# reza-power.net
KiCad netlist of a schematic drawn in EAGLE
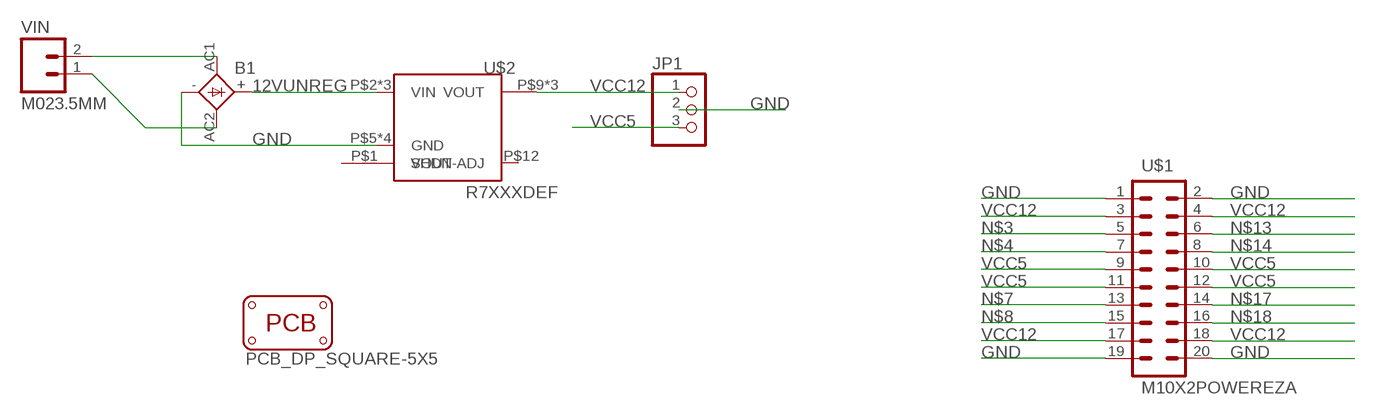
[diagram p0: schematic, sheet 1]

(export (version "E")
  (design (tool "Eeschema 10.0.6"))
  (components
    (comp (ref "B1")
      (value "1KAB")
      (footprint "eagle-import:1KAB")
      (libsource (lib "eagle-import") (part "1KAB"))
    )
    (comp (ref "JP1")
      (value "PINHD-1X3CB")
      (footprint "eagle-import:1X03-CLEANBIG")
      (libsource (lib "eagle-import") (part "PINHD-1X3CB"))
    )
    (comp (ref "PCB1")
      (value "PCB_DP_SQUARE-5X5")
      (footprint "eagle-import:DP5050_V1")
      (libsource (lib "eagle-import") (part "PCB_DP_SQUARE-5X5"))
    )
    (comp (ref "U$1")
      (value "M10X2POWEREZA")
      (footprint "eagle-import:REZAPOWER_INTERBOARD")
      (libsource (lib "eagle-import") (part "M10X2POWEREZA"))
    )
    (comp (ref "U$2")
      (value "R7XXXDEF")
      (footprint "eagle-import:1X12_RECOM")
      (libsource (lib "eagle-import") (part "R7XXXDEF"))
    )
    (comp (ref "VIN")
      (value "M023.5MM")
      (footprint "eagle-import:SCREWTERMINAL-3.5MM-2")
      (libsource (lib "eagle-import") (part "M023.5MM"))
    )
  )
  (nets
    (net (code "1") (name "/12VUNREG") (class "Default")
      (node (ref "B1") (pin "+") (pinfunction "+_+") (pintype "passive"))
      (node (ref "U$2") (pin "P$2") (pinfunction "VIN_P$2") (pintype "bidirectional"))
      (node (ref "U$2") (pin "P$3") (pinfunction "VIN_P$3") (pintype "bidirectional"))
      (node (ref "U$2") (pin "P$4") (pinfunction "VIN_P$4") (pintype "bidirectional"))
    )
    (net (code "2") (name "/GND") (class "Default")
      (node (ref "B1") (pin "-") (pinfunction "-_-") (pintype "passive"))
      (node (ref "JP1") (pin "2") (pinfunction "2_2") (pintype "passive"))
      (node (ref "U$1") (pin "1") (pinfunction "1_1") (pintype "passive"))
      (node (ref "U$1") (pin "19") (pinfunction "19_19") (pintype "passive"))
      (node (ref "U$1") (pin "2") (pinfunction "2_2") (pintype "passive"))
      (node (ref "U$1") (pin "20") (pinfunction "20_20") (pintype "passive"))
      (node (ref "U$2") (pin "P$5") (pinfunction "GND_P$5") (pintype "bidirectional"))
      (node (ref "U$2") (pin "P$6") (pinfunction "GND_P$6") (pintype "bidirectional"))
      (node (ref "U$2") (pin "P$7") (pinfunction "GND_P$7") (pintype "bidirectional"))
      (node (ref "U$2") (pin "P$8") (pinfunction "GND_P$8") (pintype "bidirectional"))
    )
    (net (code "3") (name "/N$3") (class "Default")
      (node (ref "U$1") (pin "5") (pinfunction "5_5") (pintype "passive"))
    )
    (net (code "4") (name "/N$4") (class "Default")
      (node (ref "U$1") (pin "7") (pinfunction "7_7") (pintype "passive"))
    )
    (net (code "5") (name "/N$7") (class "Default")
      (node (ref "U$1") (pin "13") (pinfunction "13_13") (pintype "passive"))
    )
    (net (code "6") (name "/N$8") (class "Default")
      (node (ref "U$1") (pin "15") (pinfunction "15_15") (pintype "passive"))
    )
    (net (code "7") (name "/N$13") (class "Default")
      (node (ref "U$1") (pin "6") (pinfunction "6_6") (pintype "passive"))
    )
    (net (code "8") (name "/N$14") (class "Default")
      (node (ref "U$1") (pin "8") (pinfunction "8_8") (pintype "passive"))
    )
    (net (code "9") (name "/N$17") (class "Default")
      (node (ref "U$1") (pin "14") (pinfunction "14_14") (pintype "passive"))
    )
    (net (code "10") (name "/N$18") (class "Default")
      (node (ref "U$1") (pin "16") (pinfunction "16_16") (pintype "passive"))
    )
    (net (code "11") (name "/VCC5") (class "Default")
      (node (ref "JP1") (pin "3") (pinfunction "3_3") (pintype "passive"))
      (node (ref "U$1") (pin "10") (pinfunction "10_10") (pintype "passive"))
      (node (ref "U$1") (pin "11") (pinfunction "11_11") (pintype "passive"))
      (node (ref "U$1") (pin "12") (pinfunction "12_12") (pintype "passive"))
      (node (ref "U$1") (pin "9") (pinfunction "9_9") (pintype "passive"))
    )
    (net (code "12") (name "/VCC12") (class "Default")
      (node (ref "JP1") (pin "1") (pinfunction "1_1") (pintype "passive"))
      (node (ref "U$1") (pin "17") (pinfunction "17_17") (pintype "passive"))
      (node (ref "U$1") (pin "18") (pinfunction "18_18") (pintype "passive"))
      (node (ref "U$1") (pin "3") (pinfunction "3_3") (pintype "passive"))
      (node (ref "U$1") (pin "4") (pinfunction "4_4") (pintype "passive"))
      (node (ref "U$2") (pin "P$10") (pinfunction "VOUT_P$10") (pintype "bidirectional"))
      (node (ref "U$2") (pin "P$11") (pinfunction "VOUT_P$11") (pintype "bidirectional"))
      (node (ref "U$2") (pin "P$9") (pinfunction "VOUT_P$9") (pintype "bidirectional"))
    )
    (net (code "13") (name "Net-(B1-PadAC1)") (class "Default")
      (node (ref "B1") (pin "AC1") (pinfunction "AC1_AC1") (pintype "passive"))
      (node (ref "VIN") (pin "2") (pinfunction "2_2") (pintype "passive"))
    )
    (net (code "14") (name "Net-(B1-PadAC2)") (class "Default")
      (node (ref "B1") (pin "AC2") (pinfunction "AC2_AC2") (pintype "passive"))
      (node (ref "VIN") (pin "1") (pinfunction "1_1") (pintype "passive"))
    )
    (net (code "15") (name "unconnected-(U$2-SHDN-PadP$1)") (class "Default")
      (node (ref "U$2") (pin "P$1") (pinfunction "SHDN_P$1") (pintype "bidirectional"))
    )
    (net (code "16") (name "unconnected-(U$2-VOUT-ADJ-PadP$12)") (class "Default")
      (node (ref "U$2") (pin "P$12") (pinfunction "VOUT-ADJ_P$12") (pintype "bidirectional"))
    )
  )
)
